# LED.net
KiCad netlist of a schematic drawn in Altium Designer
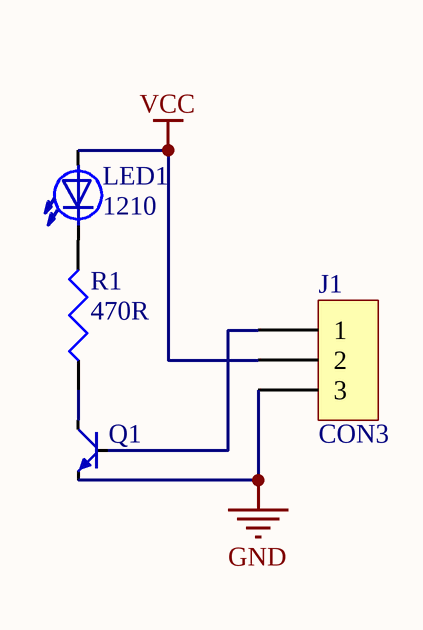
[diagram p0: LED.SchDoc]

(export (version "E")
  (design (tool "Eeschema 10.0.6"))
  (components
    (comp (ref "J1")
      (value "CON3")
      (footprint "DevModule")
      (description "Connector")
      (libsource (lib "CON系列") (part "CON3"))
    )
    (comp (ref "LED1") (value "1210") (footprint "C1210_N") (libsource (lib "二极管") (part "LED_3")))
    (comp (ref "Q1")
      (value "BJT_NPN")
      (footprint "PCB_IntegratedCircuit:SOT23-3")
      (description "Transistor")
      (libsource (lib "SCH_Active") (part "BJT_NPN"))
    )
    (comp (ref "R1") (value "470R") (footprint "6-0805_N") (libsource (lib "电阻器") (part "RES1_1")))
  )
  (nets
    (net (code "1") (name "GND") (class "Default")
      (node (ref "J1") (pin "3") (pinfunction "3_3") (pintype "passive"))
      (node (ref "Q1") (pin "2") (pinfunction "E_2") (pintype "passive"))
    )
    (net (code "2") (name "Net-(LED1-K)") (class "Default")
      (node (ref "LED1") (pin "2") (pinfunction "K_2") (pintype "passive"))
      (node (ref "R1") (pin "2") (pinfunction "2_2") (pintype "passive"))
    )
    (net (code "3") (name "Net-(Q1-B)") (class "Default")
      (node (ref "J1") (pin "1") (pinfunction "1_1") (pintype "passive"))
      (node (ref "Q1") (pin "1") (pinfunction "B_1") (pintype "passive"))
    )
    (net (code "4") (name "Net-(Q1-C)") (class "Default")
      (node (ref "Q1") (pin "3") (pinfunction "C_3") (pintype "passive"))
      (node (ref "R1") (pin "1") (pinfunction "1_1") (pintype "passive"))
    )
    (net (code "5") (name "VCC") (class "Default")
      (node (ref "J1") (pin "2") (pinfunction "2_2") (pintype "passive"))
      (node (ref "LED1") (pin "1") (pinfunction "A_1") (pintype "passive"))
    )
  )
)
